# bga_test.net
KiCad netlist of a schematic drawn in EAGLE
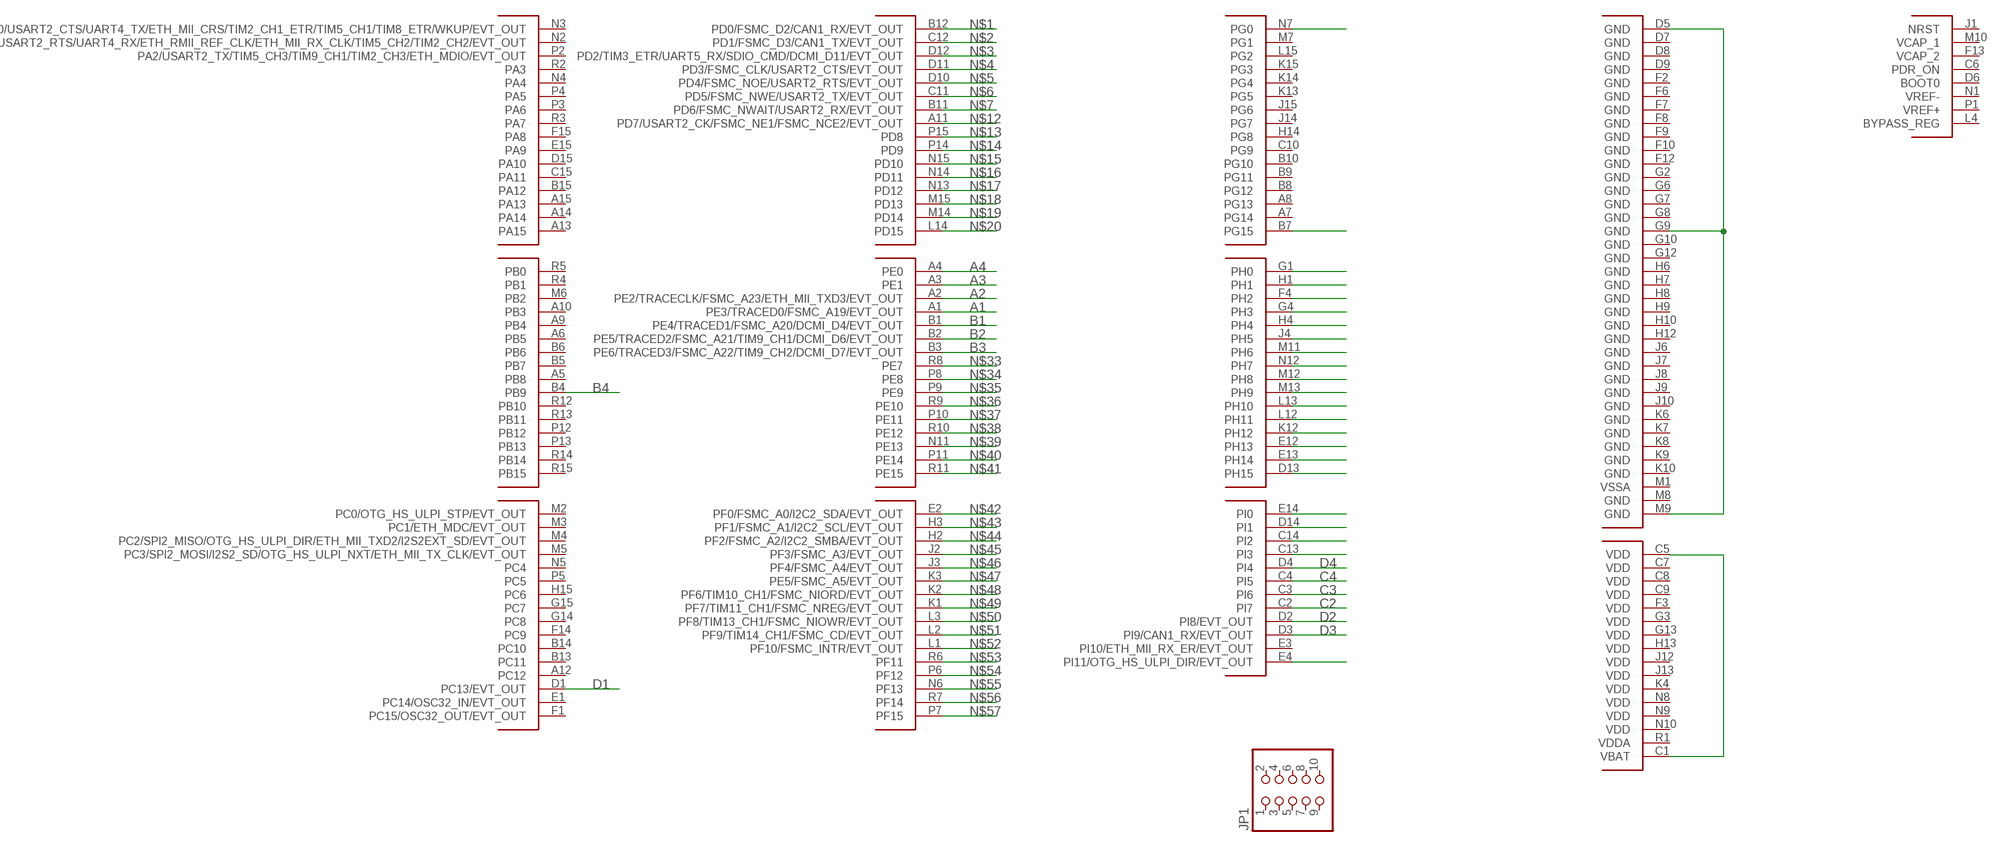
[diagram p0: schematic, sheet 1]
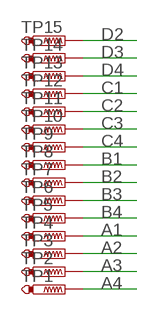
[diagram p1: schematic, sheet 2]

(export (version "E")
  (design (tool "Eeschema 10.0.6"))
  (components
    (comp (ref "TP1")
      (value "PTR1TP06R")
      (footprint "eagle-import:TP06R")
      (libsource (lib "eagle-import") (part "PTR1TP06R"))
    )
    (comp (ref "TP2")
      (value "PTR1TP06R")
      (footprint "eagle-import:TP06R")
      (libsource (lib "eagle-import") (part "PTR1TP06R"))
    )
    (comp (ref "TP3")
      (value "PTR1TP06R")
      (footprint "eagle-import:TP06R")
      (libsource (lib "eagle-import") (part "PTR1TP06R"))
    )
    (comp (ref "TP4")
      (value "PTR1TP06R")
      (footprint "eagle-import:TP06R")
      (libsource (lib "eagle-import") (part "PTR1TP06R"))
    )
    (comp (ref "TP5")
      (value "PTR1TP06R")
      (footprint "eagle-import:TP06R")
      (libsource (lib "eagle-import") (part "PTR1TP06R"))
    )
    (comp (ref "TP6")
      (value "PTR1TP06R")
      (footprint "eagle-import:TP06R")
      (libsource (lib "eagle-import") (part "PTR1TP06R"))
    )
    (comp (ref "TP7")
      (value "PTR1TP06R")
      (footprint "eagle-import:TP06R")
      (libsource (lib "eagle-import") (part "PTR1TP06R"))
    )
    (comp (ref "TP8")
      (value "PTR1TP06R")
      (footprint "eagle-import:TP06R")
      (libsource (lib "eagle-import") (part "PTR1TP06R"))
    )
    (comp (ref "TP9")
      (value "PTR1TP06R")
      (footprint "eagle-import:TP06R")
      (libsource (lib "eagle-import") (part "PTR1TP06R"))
    )
    (comp (ref "TP10")
      (value "PTR1TP06R")
      (footprint "eagle-import:TP06R")
      (libsource (lib "eagle-import") (part "PTR1TP06R"))
    )
    (comp (ref "TP11")
      (value "PTR1TP06R")
      (footprint "eagle-import:TP06R")
      (libsource (lib "eagle-import") (part "PTR1TP06R"))
    )
    (comp (ref "TP12")
      (value "PTR1TP06R")
      (footprint "eagle-import:TP06R")
      (libsource (lib "eagle-import") (part "PTR1TP06R"))
    )
    (comp (ref "TP13")
      (value "PTR1TP06R")
      (footprint "eagle-import:TP06R")
      (libsource (lib "eagle-import") (part "PTR1TP06R"))
    )
    (comp (ref "TP14")
      (value "PTR1TP06R")
      (footprint "eagle-import:TP06R")
      (libsource (lib "eagle-import") (part "PTR1TP06R"))
    )
    (comp (ref "TP15")
      (value "PTR1TP06R")
      (footprint "eagle-import:TP06R")
      (libsource (lib "eagle-import") (part "PTR1TP06R"))
    )
    (comp (ref "JP1")
      (value "PINHD-2X5")
      (footprint "eagle-import:2X05")
      (libsource (lib "eagle-import") (part "PINHD-2X5"))
    )
    (comp (ref "U$1")
      (value "STM32_32BIT_MCU_STM32F407IG")
      (footprint "eagle-import:STM32_32BIT_MCU_UFBGA176+25")
      (libsource (lib "eagle-import") (part "STM32_32BIT_MCU_STM32F407IG"))
    )
  )
  (nets
    (net (code "1") (name "A1") (class "Default")
      (node (ref "TP4") (pin "TP") (pinfunction "TP_TP") (pintype "input"))
      (node (ref "U$1") (pin "A1") (pinfunction "PE3/TRACED0/FSMC_A19/EVT_OUT_A1") (pintype "bidirectional"))
    )
    (net (code "2") (name "A2") (class "Default")
      (node (ref "TP3") (pin "TP") (pinfunction "TP_TP") (pintype "input"))
      (node (ref "U$1") (pin "A2") (pinfunction "PE2/TRACECLK/FSMC_A23/ETH_MII_TXD3/EVT_OUT_A2") (pintype "bidirectional"))
    )
    (net (code "3") (name "A3") (class "Default")
      (node (ref "TP2") (pin "TP") (pinfunction "TP_TP") (pintype "input"))
      (node (ref "U$1") (pin "A3") (pinfunction "PE1_A3") (pintype "bidirectional"))
    )
    (net (code "4") (name "A4") (class "Default")
      (node (ref "TP1") (pin "TP") (pinfunction "TP_TP") (pintype "input"))
      (node (ref "U$1") (pin "A4") (pinfunction "PE0_A4") (pintype "bidirectional"))
    )
    (net (code "5") (name "B1") (class "Default")
      (node (ref "TP8") (pin "TP") (pinfunction "TP_TP") (pintype "input"))
      (node (ref "U$1") (pin "B1") (pinfunction "PE4/TRACED1/FSMC_A20/DCMI_D4/EVT_OUT_B1") (pintype "bidirectional"))
    )
    (net (code "6") (name "B2") (class "Default")
      (node (ref "TP7") (pin "TP") (pinfunction "TP_TP") (pintype "input"))
      (node (ref "U$1") (pin "B2") (pinfunction "PE5/TRACED2/FSMC_A21/TIM9_CH1/DCMI_D6/EVT_OUT_B2") (pintype "bidirectional"))
    )
    (net (code "7") (name "B3") (class "Default")
      (node (ref "TP6") (pin "TP") (pinfunction "TP_TP") (pintype "input"))
      (node (ref "U$1") (pin "B3") (pinfunction "PE6/TRACED3/FSMC_A22/TIM9_CH2/DCMI_D7/EVT_OUT_B3") (pintype "bidirectional"))
    )
    (net (code "8") (name "B4") (class "Default")
      (node (ref "TP5") (pin "TP") (pinfunction "TP_TP") (pintype "input"))
      (node (ref "U$1") (pin "B4") (pinfunction "PB9_B4") (pintype "bidirectional"))
    )
    (net (code "9") (name "C1") (class "Default")
      (node (ref "TP12") (pin "TP") (pinfunction "TP_TP") (pintype "input"))
    )
    (net (code "10") (name "C2") (class "Default")
      (node (ref "TP11") (pin "TP") (pinfunction "TP_TP") (pintype "input"))
      (node (ref "U$1") (pin "C2") (pinfunction "PI7_C2") (pintype "bidirectional"))
    )
    (net (code "11") (name "C3") (class "Default")
      (node (ref "TP10") (pin "TP") (pinfunction "TP_TP") (pintype "input"))
      (node (ref "U$1") (pin "C3") (pinfunction "PI6_C3") (pintype "bidirectional"))
    )
    (net (code "12") (name "C4") (class "Default")
      (node (ref "TP9") (pin "TP") (pinfunction "TP_TP") (pintype "input"))
      (node (ref "U$1") (pin "C4") (pinfunction "PI5_C4") (pintype "bidirectional"))
    )
    (net (code "13") (name "D1") (class "Default")
      (node (ref "U$1") (pin "D1") (pinfunction "PC13/EVT_OUT_D1") (pintype "bidirectional"))
    )
    (net (code "14") (name "D2") (class "Default")
      (node (ref "TP15") (pin "TP") (pinfunction "TP_TP") (pintype "input"))
      (node (ref "U$1") (pin "D2") (pinfunction "PI8/EVT_OUT_D2") (pintype "bidirectional"))
    )
    (net (code "15") (name "D3") (class "Default")
      (node (ref "TP14") (pin "TP") (pinfunction "TP_TP") (pintype "input"))
      (node (ref "U$1") (pin "D3") (pinfunction "PI9/CAN1_RX/EVT_OUT_D3") (pintype "bidirectional"))
    )
    (net (code "16") (name "D4") (class "Default")
      (node (ref "TP13") (pin "TP") (pinfunction "TP_TP") (pintype "input"))
      (node (ref "U$1") (pin "D4") (pinfunction "PI4_D4") (pintype "bidirectional"))
    )
    (net (code "17") (name "N$1") (class "Default")
      (node (ref "U$1") (pin "B12") (pinfunction "PD0/FSMC_D2/CAN1_RX/EVT_OUT_B12") (pintype "bidirectional"))
    )
    (net (code "18") (name "N$2") (class "Default")
      (node (ref "U$1") (pin "C12") (pinfunction "PD1/FSMC_D3/CAN1_TX/EVT_OUT_C12") (pintype "bidirectional"))
    )
    (net (code "19") (name "N$3") (class "Default")
      (node (ref "U$1") (pin "D12") (pinfunction "PD2/TIM3_ETR/UART5_RX/SDIO_CMD/DCMI_D11/EVT_OUT_D12") (pintype "bidirectional"))
    )
    (net (code "20") (name "N$4") (class "Default")
      (node (ref "U$1") (pin "D11") (pinfunction "PD3/FSMC_CLK/USART2_CTS/EVT_OUT_D11") (pintype "bidirectional"))
    )
    (net (code "21") (name "N$5") (class "Default")
      (node (ref "U$1") (pin "D10") (pinfunction "PD4/FSMC_NOE/USART2_RTS/EVT_OUT_D10") (pintype "bidirectional"))
    )
    (net (code "22") (name "N$6") (class "Default")
      (node (ref "U$1") (pin "C11") (pinfunction "PD5/FSMC_NWE/USART2_TX/EVT_OUT_C11") (pintype "bidirectional"))
    )
    (net (code "23") (name "N$7") (class "Default")
      (node (ref "U$1") (pin "B11") (pinfunction "PD6/FSMC_NWAIT/USART2_RX/EVT_OUT_B11") (pintype "bidirectional"))
    )
    (net (code "24") (name "N$12") (class "Default")
      (node (ref "U$1") (pin "A11") (pinfunction "PD7/USART2_CK/FSMC_NE1/FSMC_NCE2/EVT_OUT_A11") (pintype "bidirectional"))
    )
    (net (code "25") (name "N$13") (class "Default")
      (node (ref "U$1") (pin "P15") (pinfunction "PD8_P15") (pintype "bidirectional"))
    )
    (net (code "26") (name "N$14") (class "Default")
      (node (ref "U$1") (pin "P14") (pinfunction "PD9_P14") (pintype "bidirectional"))
    )
    (net (code "27") (name "N$15") (class "Default")
      (node (ref "U$1") (pin "N15") (pinfunction "PD10_N15") (pintype "bidirectional"))
    )
    (net (code "28") (name "N$16") (class "Default")
      (node (ref "U$1") (pin "N14") (pinfunction "PD11_N14") (pintype "bidirectional"))
    )
    (net (code "29") (name "N$17") (class "Default")
      (node (ref "U$1") (pin "N13") (pinfunction "PD12_N13") (pintype "bidirectional"))
    )
    (net (code "30") (name "N$18") (class "Default")
      (node (ref "U$1") (pin "M15") (pinfunction "PD13_M15") (pintype "bidirectional"))
    )
    (net (code "31") (name "N$19") (class "Default")
      (node (ref "U$1") (pin "M14") (pinfunction "PD14_M14") (pintype "bidirectional"))
    )
    (net (code "32") (name "N$20") (class "Default")
      (node (ref "U$1") (pin "L14") (pinfunction "PD15_L14") (pintype "bidirectional"))
    )
    (net (code "33") (name "N$33") (class "Default")
      (node (ref "U$1") (pin "R8") (pinfunction "PE7_R8") (pintype "bidirectional"))
    )
    (net (code "34") (name "N$34") (class "Default")
      (node (ref "U$1") (pin "P8") (pinfunction "PE8_P8") (pintype "bidirectional"))
    )
    (net (code "35") (name "N$35") (class "Default")
      (node (ref "U$1") (pin "P9") (pinfunction "PE9_P9") (pintype "bidirectional"))
    )
    (net (code "36") (name "N$36") (class "Default")
      (node (ref "U$1") (pin "R9") (pinfunction "PE10_R9") (pintype "bidirectional"))
    )
    (net (code "37") (name "N$37") (class "Default")
      (node (ref "U$1") (pin "P10") (pinfunction "PE11_P10") (pintype "bidirectional"))
    )
    (net (code "38") (name "N$38") (class "Default")
      (node (ref "U$1") (pin "R10") (pinfunction "PE12_R10") (pintype "bidirectional"))
    )
    (net (code "39") (name "N$39") (class "Default")
      (node (ref "U$1") (pin "N11") (pinfunction "PE13_N11") (pintype "bidirectional"))
    )
    (net (code "40") (name "N$40") (class "Default")
      (node (ref "U$1") (pin "P11") (pinfunction "PE14_P11") (pintype "bidirectional"))
    )
    (net (code "41") (name "N$41") (class "Default")
      (node (ref "U$1") (pin "R11") (pinfunction "PE15_R11") (pintype "bidirectional"))
    )
    (net (code "42") (name "N$42") (class "Default")
      (node (ref "U$1") (pin "E2") (pinfunction "PF0/FSMC_A0/I2C2_SDA/EVT_OUT_E2") (pintype "bidirectional"))
    )
    (net (code "43") (name "N$43") (class "Default")
      (node (ref "U$1") (pin "H3") (pinfunction "PF1/FSMC_A1/I2C2_SCL/EVT_OUT_H3") (pintype "bidirectional"))
    )
    (net (code "44") (name "N$44") (class "Default")
      (node (ref "U$1") (pin "H2") (pinfunction "PF2/FSMC_A2/I2C2_SMBA/EVT_OUT_H2") (pintype "bidirectional"))
    )
    (net (code "45") (name "N$45") (class "Default")
      (node (ref "U$1") (pin "J2") (pinfunction "PF3/FSMC_A3/EVT_OUT_J2") (pintype "bidirectional"))
    )
    (net (code "46") (name "N$46") (class "Default")
      (node (ref "U$1") (pin "J3") (pinfunction "PF4/FSMC_A4/EVT_OUT_J3") (pintype "bidirectional"))
    )
    (net (code "47") (name "N$47") (class "Default")
      (node (ref "U$1") (pin "K3") (pinfunction "PE5/FSMC_A5/EVT_OUT_K3") (pintype "bidirectional"))
    )
    (net (code "48") (name "N$48") (class "Default")
      (node (ref "U$1") (pin "K2") (pinfunction "PF6/TIM10_CH1/FSMC_NIORD/EVT_OUT_K2") (pintype "bidirectional"))
    )
    (net (code "49") (name "N$49") (class "Default")
      (node (ref "U$1") (pin "K1") (pinfunction "PF7/TIM11_CH1/FSMC_NREG/EVT_OUT_K1") (pintype "bidirectional"))
    )
    (net (code "50") (name "N$50") (class "Default")
      (node (ref "U$1") (pin "L3") (pinfunction "PF8/TIM13_CH1/FSMC_NIOWR/EVT_OUT_L3") (pintype "bidirectional"))
    )
    (net (code "51") (name "N$51") (class "Default")
      (node (ref "U$1") (pin "L2") (pinfunction "PF9/TIM14_CH1/FSMC_CD/EVT_OUT_L2") (pintype "bidirectional"))
    )
    (net (code "52") (name "N$52") (class "Default")
      (node (ref "U$1") (pin "L1") (pinfunction "PF10/FSMC_INTR/EVT_OUT_L1") (pintype "bidirectional"))
    )
    (net (code "53") (name "N$53") (class "Default")
      (node (ref "U$1") (pin "R6") (pinfunction "PF11_R6") (pintype "bidirectional"))
    )
    (net (code "54") (name "N$54") (class "Default")
      (node (ref "U$1") (pin "P6") (pinfunction "PF12_P6") (pintype "bidirectional"))
    )
    (net (code "55") (name "N$55") (class "Default")
      (node (ref "U$1") (pin "N6") (pinfunction "PF13_N6") (pintype "bidirectional"))
    )
    (net (code "56") (name "N$56") (class "Default")
      (node (ref "U$1") (pin "R7") (pinfunction "PF14_R7") (pintype "bidirectional"))
    )
    (net (code "57") (name "N$57") (class "Default")
      (node (ref "U$1") (pin "P7") (pinfunction "PF15_P7") (pintype "bidirectional"))
    )
    (net (code "58") (name "Net-(U$1-GND-PadD5)") (class "Default")
      (node (ref "U$1") (pin "D5") (pinfunction "GND_D5") (pintype "bidirectional"))
      (node (ref "U$1") (pin "G9") (pinfunction "GND_G9") (pintype "bidirectional"))
      (node (ref "U$1") (pin "M9") (pinfunction "GND_M9") (pintype "bidirectional"))
    )
    (net (code "59") (name "Net-(U$1-VBAT)") (class "Default")
      (node (ref "U$1") (pin "C1") (pinfunction "VBAT_C1") (pintype "bidirectional"))
      (node (ref "U$1") (pin "C5") (pinfunction "VDD_C5") (pintype "bidirectional"))
    )
    (net (code "60") (name "unconnected-(JP1-Pad1)") (class "Default")
      (node (ref "JP1") (pin "1") (pinfunction "1_1") (pintype "passive"))
    )
    (net (code "61") (name "unconnected-(JP1-Pad2)") (class "Default")
      (node (ref "JP1") (pin "2") (pinfunction "2_2") (pintype "passive"))
    )
    (net (code "62") (name "unconnected-(JP1-Pad3)") (class "Default")
      (node (ref "JP1") (pin "3") (pinfunction "3_3") (pintype "passive"))
    )
    (net (code "63") (name "unconnected-(JP1-Pad4)") (class "Default")
      (node (ref "JP1") (pin "4") (pinfunction "4_4") (pintype "passive"))
    )
    (net (code "64") (name "unconnected-(JP1-Pad5)") (class "Default")
      (node (ref "JP1") (pin "5") (pinfunction "5_5") (pintype "passive"))
    )
    (net (code "65") (name "unconnected-(JP1-Pad6)") (class "Default")
      (node (ref "JP1") (pin "6") (pinfunction "6_6") (pintype "passive"))
    )
    (net (code "66") (name "unconnected-(JP1-Pad7)") (class "Default")
      (node (ref "JP1") (pin "7") (pinfunction "7_7") (pintype "passive"))
    )
    (net (code "67") (name "unconnected-(JP1-Pad8)") (class "Default")
      (node (ref "JP1") (pin "8") (pinfunction "8_8") (pintype "passive"))
    )
    (net (code "68") (name "unconnected-(JP1-Pad9)") (class "Default")
      (node (ref "JP1") (pin "9") (pinfunction "9_9") (pintype "passive"))
    )
    (net (code "69") (name "unconnected-(JP1-Pad10)") (class "Default")
      (node (ref "JP1") (pin "10") (pinfunction "10_10") (pintype "passive"))
    )
    (net (code "70") (name "unconnected-(U$1-BOOT0-PadD6)") (class "Default")
      (node (ref "U$1") (pin "D6") (pinfunction "BOOT0_D6") (pintype "bidirectional"))
    )
    (net (code "71") (name "unconnected-(U$1-BYPASS_REG-PadL4)") (class "Default")
      (node (ref "U$1") (pin "L4") (pinfunction "BYPASS_REG_L4") (pintype "bidirectional"))
    )
    (net (code "72") (name "unconnected-(U$1-GND-PadD7)") (class "Default")
      (node (ref "U$1") (pin "D7") (pinfunction "GND_D7") (pintype "bidirectional"))
    )
    (net (code "73") (name "unconnected-(U$1-GND-PadD8)") (class "Default")
      (node (ref "U$1") (pin "D8") (pinfunction "GND_D8") (pintype "bidirectional"))
    )
    (net (code "74") (name "unconnected-(U$1-GND-PadD9)") (class "Default")
      (node (ref "U$1") (pin "D9") (pinfunction "GND_D9") (pintype "bidirectional"))
    )
    (net (code "75") (name "unconnected-(U$1-GND-PadF2)") (class "Default")
      (node (ref "U$1") (pin "F2") (pinfunction "GND_F2") (pintype "bidirectional"))
    )
    (net (code "76") (name "unconnected-(U$1-GND-PadF6)") (class "Default")
      (node (ref "U$1") (pin "F6") (pinfunction "GND_F6") (pintype "bidirectional"))
    )
    (net (code "77") (name "unconnected-(U$1-GND-PadF7)") (class "Default")
      (node (ref "U$1") (pin "F7") (pinfunction "GND_F7") (pintype "bidirectional"))
    )
    (net (code "78") (name "unconnected-(U$1-GND-PadF8)") (class "Default")
      (node (ref "U$1") (pin "F8") (pinfunction "GND_F8") (pintype "bidirectional"))
    )
    (net (code "79") (name "unconnected-(U$1-GND-PadF9)") (class "Default")
      (node (ref "U$1") (pin "F9") (pinfunction "GND_F9") (pintype "bidirectional"))
    )
    (net (code "80") (name "unconnected-(U$1-GND-PadF10)") (class "Default")
      (node (ref "U$1") (pin "F10") (pinfunction "GND_F10") (pintype "bidirectional"))
    )
    (net (code "81") (name "unconnected-(U$1-GND-PadF12)") (class "Default")
      (node (ref "U$1") (pin "F12") (pinfunction "GND_F12") (pintype "bidirectional"))
    )
    (net (code "82") (name "unconnected-(U$1-GND-PadG2)") (class "Default")
      (node (ref "U$1") (pin "G2") (pinfunction "GND_G2") (pintype "bidirectional"))
    )
    (net (code "83") (name "unconnected-(U$1-GND-PadG6)") (class "Default")
      (node (ref "U$1") (pin "G6") (pinfunction "GND_G6") (pintype "bidirectional"))
    )
    (net (code "84") (name "unconnected-(U$1-GND-PadG7)") (class "Default")
      (node (ref "U$1") (pin "G7") (pinfunction "GND_G7") (pintype "bidirectional"))
    )
    (net (code "85") (name "unconnected-(U$1-GND-PadG8)") (class "Default")
      (node (ref "U$1") (pin "G8") (pinfunction "GND_G8") (pintype "bidirectional"))
    )
    (net (code "86") (name "unconnected-(U$1-GND-PadG10)") (class "Default")
      (node (ref "U$1") (pin "G10") (pinfunction "GND_G10") (pintype "bidirectional"))
    )
    (net (code "87") (name "unconnected-(U$1-GND-PadG12)") (class "Default")
      (node (ref "U$1") (pin "G12") (pinfunction "GND_G12") (pintype "bidirectional"))
    )
    (net (code "88") (name "unconnected-(U$1-GND-PadH6)") (class "Default")
      (node (ref "U$1") (pin "H6") (pinfunction "GND_H6") (pintype "bidirectional"))
    )
    (net (code "89") (name "unconnected-(U$1-GND-PadH7)") (class "Default")
      (node (ref "U$1") (pin "H7") (pinfunction "GND_H7") (pintype "bidirectional"))
    )
    (net (code "90") (name "unconnected-(U$1-GND-PadH8)") (class "Default")
      (node (ref "U$1") (pin "H8") (pinfunction "GND_H8") (pintype "bidirectional"))
    )
    (net (code "91") (name "unconnected-(U$1-GND-PadH9)") (class "Default")
      (node (ref "U$1") (pin "H9") (pinfunction "GND_H9") (pintype "bidirectional"))
    )
    (net (code "92") (name "unconnected-(U$1-GND-PadH10)") (class "Default")
      (node (ref "U$1") (pin "H10") (pinfunction "GND_H10") (pintype "bidirectional"))
    )
    (net (code "93") (name "unconnected-(U$1-GND-PadH12)") (class "Default")
      (node (ref "U$1") (pin "H12") (pinfunction "GND_H12") (pintype "bidirectional"))
    )
    (net (code "94") (name "unconnected-(U$1-GND-PadJ6)") (class "Default")
      (node (ref "U$1") (pin "J6") (pinfunction "GND_J6") (pintype "bidirectional"))
    )
    (net (code "95") (name "unconnected-(U$1-GND-PadJ7)") (class "Default")
      (node (ref "U$1") (pin "J7") (pinfunction "GND_J7") (pintype "bidirectional"))
    )
    (net (code "96") (name "unconnected-(U$1-GND-PadJ8)") (class "Default")
      (node (ref "U$1") (pin "J8") (pinfunction "GND_J8") (pintype "bidirectional"))
    )
    (net (code "97") (name "unconnected-(U$1-GND-PadJ9)") (class "Default")
      (node (ref "U$1") (pin "J9") (pinfunction "GND_J9") (pintype "bidirectional"))
    )
    (net (code "98") (name "unconnected-(U$1-GND-PadJ10)") (class "Default")
      (node (ref "U$1") (pin "J10") (pinfunction "GND_J10") (pintype "bidirectional"))
    )
    (net (code "99") (name "unconnected-(U$1-GND-PadK6)") (class "Default")
      (node (ref "U$1") (pin "K6") (pinfunction "GND_K6") (pintype "bidirectional"))
    )
    (net (code "100") (name "unconnected-(U$1-GND-PadK7)") (class "Default")
      (node (ref "U$1") (pin "K7") (pinfunction "GND_K7") (pintype "bidirectional"))
    )
    (net (code "101") (name "unconnected-(U$1-GND-PadK8)") (class "Default")
      (node (ref "U$1") (pin "K8") (pinfunction "GND_K8") (pintype "bidirectional"))
    )
    (net (code "102") (name "unconnected-(U$1-GND-PadK9)") (class "Default")
      (node (ref "U$1") (pin "K9") (pinfunction "GND_K9") (pintype "bidirectional"))
    )
    (net (code "103") (name "unconnected-(U$1-GND-PadK10)") (class "Default")
      (node (ref "U$1") (pin "K10") (pinfunction "GND_K10") (pintype "bidirectional"))
    )
    (net (code "104") (name "unconnected-(U$1-GND-PadM8)") (class "Default")
      (node (ref "U$1") (pin "M8") (pinfunction "GND_M8") (pintype "bidirectional"))
    )
    (net (code "105") (name "unconnected-(U$1-NRST-PadJ1)") (class "Default")
      (node (ref "U$1") (pin "J1") (pinfunction "NRST_J1") (pintype "bidirectional"))
    )
    (net (code "106") (name "unconnected-(U$1-PA0{slash}USART2_CTS{slash}UART4_TX{slash}ETH_MII_CRS{slash}TIM2_CH1_ETR{slash}TIM5_CH1{slash}TIM8_ETR{slash}WKUP{slash}EVT_OUT-PadN3)") (class "Default")
      (node (ref "U$1") (pin "N3") (pinfunction "PA0/USART2_CTS/UART4_TX/ETH_MII_CRS/TIM2_CH1_ETR/TIM5_CH1/TIM8_ETR/WKUP/EVT_OUT_N3") (pintype "bidirectional"))
    )
    (net (code "107") (name "unconnected-(U$1-PA1{slash}USART2_RTS{slash}UART4_RX{slash}ETH_RMII_REF_CLK{slash}ETH_MII_RX_CLK{slash}TIM5_CH2{slash}TIM2_CH2{slash}EVT_OUT-PadN2)") (class "Default")
      (node (ref "U$1") (pin "N2") (pinfunction "PA1/USART2_RTS/UART4_RX/ETH_RMII_REF_CLK/ETH_MII_RX_CLK/TIM5_CH2/TIM2_CH2/EVT_OUT_N2") (pintype "bidirectional"))
    )
    (net (code "108") (name "unconnected-(U$1-PA2{slash}USART2_TX{slash}TIM5_CH3{slash}TIM9_CH1{slash}TIM2_CH3{slash}ETH_MDIO{slash}EVT_OUT-PadP2)") (class "Default")
      (node (ref "U$1") (pin "P2") (pinfunction "PA2/USART2_TX/TIM5_CH3/TIM9_CH1/TIM2_CH3/ETH_MDIO/EVT_OUT_P2") (pintype "bidirectional"))
    )
    (net (code "109") (name "unconnected-(U$1-PA3-PadR2)") (class "Default")
      (node (ref "U$1") (pin "R2") (pinfunction "PA3_R2") (pintype "bidirectional"))
    )
    (net (code "110") (name "unconnected-(U$1-PA4-PadN4)") (class "Default")
      (node (ref "U$1") (pin "N4") (pinfunction "PA4_N4") (pintype "bidirectional"))
    )
    (net (code "111") (name "unconnected-(U$1-PA5-PadP4)") (class "Default")
      (node (ref "U$1") (pin "P4") (pinfunction "PA5_P4") (pintype "bidirectional"))
    )
    (net (code "112") (name "unconnected-(U$1-PA6-PadP3)") (class "Default")
      (node (ref "U$1") (pin "P3") (pinfunction "PA6_P3") (pintype "bidirectional"))
    )
    (net (code "113") (name "unconnected-(U$1-PA7-PadR3)") (class "Default")
      (node (ref "U$1") (pin "R3") (pinfunction "PA7_R3") (pintype "bidirectional"))
    )
    (net (code "114") (name "unconnected-(U$1-PA8-PadF15)") (class "Default")
      (node (ref "U$1") (pin "F15") (pinfunction "PA8_F15") (pintype "bidirectional"))
    )
    (net (code "115") (name "unconnected-(U$1-PA9-PadE15)") (class "Default")
      (node (ref "U$1") (pin "E15") (pinfunction "PA9_E15") (pintype "bidirectional"))
    )
    (net (code "116") (name "unconnected-(U$1-PA10-PadD15)") (class "Default")
      (node (ref "U$1") (pin "D15") (pinfunction "PA10_D15") (pintype "bidirectional"))
    )
    (net (code "117") (name "unconnected-(U$1-PA11-PadC15)") (class "Default")
      (node (ref "U$1") (pin "C15") (pinfunction "PA11_C15") (pintype "bidirectional"))
    )
    (net (code "118") (name "unconnected-(U$1-PA12-PadB15)") (class "Default")
      (node (ref "U$1") (pin "B15") (pinfunction "PA12_B15") (pintype "bidirectional"))
    )
    (net (code "119") (name "unconnected-(U$1-PA13-PadA15)") (class "Default")
      (node (ref "U$1") (pin "A15") (pinfunction "PA13_A15") (pintype "bidirectional"))
    )
    (net (code "120") (name "unconnected-(U$1-PA14-PadA14)") (class "Default")
      (node (ref "U$1") (pin "A14") (pinfunction "PA14_A14") (pintype "bidirectional"))
    )
    (net (code "121") (name "unconnected-(U$1-PA15-PadA13)") (class "Default")
      (node (ref "U$1") (pin "A13") (pinfunction "PA15_A13") (pintype "bidirectional"))
    )
    (net (code "122") (name "unconnected-(U$1-PB0-PadR5)") (class "Default")
      (node (ref "U$1") (pin "R5") (pinfunction "PB0_R5") (pintype "bidirectional"))
    )
    (net (code "123") (name "unconnected-(U$1-PB1-PadR4)") (class "Default")
      (node (ref "U$1") (pin "R4") (pinfunction "PB1_R4") (pintype "bidirectional"))
    )
    (net (code "124") (name "unconnected-(U$1-PB2-PadM6)") (class "Default")
      (node (ref "U$1") (pin "M6") (pinfunction "PB2_M6") (pintype "bidirectional"))
    )
    (net (code "125") (name "unconnected-(U$1-PB3-PadA10)") (class "Default")
      (node (ref "U$1") (pin "A10") (pinfunction "PB3_A10") (pintype "bidirectional"))
    )
    (net (code "126") (name "unconnected-(U$1-PB4-PadA9)") (class "Default")
      (node (ref "U$1") (pin "A9") (pinfunction "PB4_A9") (pintype "bidirectional"))
    )
    (net (code "127") (name "unconnected-(U$1-PB5-PadA6)") (class "Default")
      (node (ref "U$1") (pin "A6") (pinfunction "PB5_A6") (pintype "bidirectional"))
    )
    (net (code "128") (name "unconnected-(U$1-PB6-PadB6)") (class "Default")
      (node (ref "U$1") (pin "B6") (pinfunction "PB6_B6") (pintype "bidirectional"))
    )
    (net (code "129") (name "unconnected-(U$1-PB7-PadB5)") (class "Default")
      (node (ref "U$1") (pin "B5") (pinfunction "PB7_B5") (pintype "bidirectional"))
    )
    (net (code "130") (name "unconnected-(U$1-PB8-PadA5)") (class "Default")
      (node (ref "U$1") (pin "A5") (pinfunction "PB8_A5") (pintype "bidirectional"))
    )
    (net (code "131") (name "unconnected-(U$1-PB10-PadR12)") (class "Default")
      (node (ref "U$1") (pin "R12") (pinfunction "PB10_R12") (pintype "bidirectional"))
    )
    (net (code "132") (name "unconnected-(U$1-PB11-PadR13)") (class "Default")
      (node (ref "U$1") (pin "R13") (pinfunction "PB11_R13") (pintype "bidirectional"))
    )
    (net (code "133") (name "unconnected-(U$1-PB12-PadP12)") (class "Default")
      (node (ref "U$1") (pin "P12") (pinfunction "PB12_P12") (pintype "bidirectional"))
    )
    (net (code "134") (name "unconnected-(U$1-PB13-PadP13)") (class "Default")
      (node (ref "U$1") (pin "P13") (pinfunction "PB13_P13") (pintype "bidirectional"))
    )
    (net (code "135") (name "unconnected-(U$1-PB14-PadR14)") (class "Default")
      (node (ref "U$1") (pin "R14") (pinfunction "PB14_R14") (pintype "bidirectional"))
    )
    (net (code "136") (name "unconnected-(U$1-PB15-PadR15)") (class "Default")
      (node (ref "U$1") (pin "R15") (pinfunction "PB15_R15") (pintype "bidirectional"))
    )
    (net (code "137") (name "unconnected-(U$1-PC0{slash}OTG_HS_ULPI_STP{slash}EVT_OUT-PadM2)") (class "Default")
      (node (ref "U$1") (pin "M2") (pinfunction "PC0/OTG_HS_ULPI_STP/EVT_OUT_M2") (pintype "bidirectional"))
    )
    (net (code "138") (name "unconnected-(U$1-PC1{slash}ETH_MDC{slash}EVT_OUT-PadM3)") (class "Default")
      (node (ref "U$1") (pin "M3") (pinfunction "PC1/ETH_MDC/EVT_OUT_M3") (pintype "bidirectional"))
    )
    (net (code "139") (name "unconnected-(U$1-PC2{slash}SPI2_MISO{slash}OTG_HS_ULPI_DIR{slash}ETH_MII_TXD2{slash}I2S2EXT_SD{slash}EVT_OUT-PadM4)") (class "Default")
      (node (ref "U$1") (pin "M4") (pinfunction "PC2/SPI2_MISO/OTG_HS_ULPI_DIR/ETH_MII_TXD2/I2S2EXT_SD/EVT_OUT_M4") (pintype "bidirectional"))
    )
    (net (code "140") (name "unconnected-(U$1-PC3{slash}SPI2_MOSI{slash}I2S2_SD{slash}OTG_HS_ULPI_NXT{slash}ETH_MII_TX_CLK{slash}EVT_OUT-PadM5)") (class "Default")
      (node (ref "U$1") (pin "M5") (pinfunction "PC3/SPI2_MOSI/I2S2_SD/OTG_HS_ULPI_NXT/ETH_MII_TX_CLK/EVT_OUT_M5") (pintype "bidirectional"))
    )
    (net (code "141") (name "unconnected-(U$1-PC4-PadN5)") (class "Default")
      (node (ref "U$1") (pin "N5") (pinfunction "PC4_N5") (pintype "bidirectional"))
    )
    (net (code "142") (name "unconnected-(U$1-PC5-PadP5)") (class "Default")
      (node (ref "U$1") (pin "P5") (pinfunction "PC5_P5") (pintype "bidirectional"))
    )
    (net (code "143") (name "unconnected-(U$1-PC6-PadH15)") (class "Default")
      (node (ref "U$1") (pin "H15") (pinfunction "PC6_H15") (pintype "bidirectional"))
    )
    (net (code "144") (name "unconnected-(U$1-PC7-PadG15)") (class "Default")
      (node (ref "U$1") (pin "G15") (pinfunction "PC7_G15") (pintype "bidirectional"))
    )
    (net (code "145") (name "unconnected-(U$1-PC8-PadG14)") (class "Default")
      (node (ref "U$1") (pin "G14") (pinfunction "PC8_G14") (pintype "bidirectional"))
    )
    (net (code "146") (name "unconnected-(U$1-PC9-PadF14)") (class "Default")
      (node (ref "U$1") (pin "F14") (pinfunction "PC9_F14") (pintype "bidirectional"))
    )
    (net (code "147") (name "unconnected-(U$1-PC10-PadB14)") (class "Default")
      (node (ref "U$1") (pin "B14") (pinfunction "PC10_B14") (pintype "bidirectional"))
    )
    (net (code "148") (name "unconnected-(U$1-PC11-PadB13)") (class "Default")
      (node (ref "U$1") (pin "B13") (pinfunction "PC11_B13") (pintype "bidirectional"))
    )
    (net (code "149") (name "unconnected-(U$1-PC12-PadA12)") (class "Default")
      (node (ref "U$1") (pin "A12") (pinfunction "PC12_A12") (pintype "bidirectional"))
    )
    (net (code "150") (name "unconnected-(U$1-PC14{slash}OSC32_IN{slash}EVT_OUT-PadE1)") (class "Default")
      (node (ref "U$1") (pin "E1") (pinfunction "PC14/OSC32_IN/EVT_OUT_E1") (pintype "bidirectional"))
    )
    (net (code "151") (name "unconnected-(U$1-PC15{slash}OSC32_OUT{slash}EVT_OUT-PadF1)") (class "Default")
      (node (ref "U$1") (pin "F1") (pinfunction "PC15/OSC32_OUT/EVT_OUT_F1") (pintype "bidirectional"))
    )
    (net (code "152") (name "unconnected-(U$1-PDR_ON-PadC6)") (class "Default")
      (node (ref "U$1") (pin "C6") (pinfunction "PDR_ON_C6") (pintype "bidirectional"))
    )
    (net (code "153") (name "unconnected-(U$1-PG0-PadN7)") (class "Default")
      (node (ref "U$1") (pin "N7") (pinfunction "PG0_N7") (pintype "bidirectional"))
    )
    (net (code "154") (name "unconnected-(U$1-PG1-PadM7)") (class "Default")
      (node (ref "U$1") (pin "M7") (pinfunction "PG1_M7") (pintype "bidirectional"))
    )
    (net (code "155") (name "unconnected-(U$1-PG2-PadL15)") (class "Default")
      (node (ref "U$1") (pin "L15") (pinfunction "PG2_L15") (pintype "bidirectional"))
    )
    (net (code "156") (name "unconnected-(U$1-PG3-PadK15)") (class "Default")
      (node (ref "U$1") (pin "K15") (pinfunction "PG3_K15") (pintype "bidirectional"))
    )
    (net (code "157") (name "unconnected-(U$1-PG4-PadK14)") (class "Default")
      (node (ref "U$1") (pin "K14") (pinfunction "PG4_K14") (pintype "bidirectional"))
    )
    (net (code "158") (name "unconnected-(U$1-PG5-PadK13)") (class "Default")
      (node (ref "U$1") (pin "K13") (pinfunction "PG5_K13") (pintype "bidirectional"))
    )
    (net (code "159") (name "unconnected-(U$1-PG6-PadJ15)") (class "Default")
      (node (ref "U$1") (pin "J15") (pinfunction "PG6_J15") (pintype "bidirectional"))
    )
    (net (code "160") (name "unconnected-(U$1-PG7-PadJ14)") (class "Default")
      (node (ref "U$1") (pin "J14") (pinfunction "PG7_J14") (pintype "bidirectional"))
    )
    (net (code "161") (name "unconnected-(U$1-PG8-PadH14)") (class "Default")
      (node (ref "U$1") (pin "H14") (pinfunction "PG8_H14") (pintype "bidirectional"))
    )
    (net (code "162") (name "unconnected-(U$1-PG9-PadC10)") (class "Default")
      (node (ref "U$1") (pin "C10") (pinfunction "PG9_C10") (pintype "bidirectional"))
    )
    (net (code "163") (name "unconnected-(U$1-PG10-PadB10)") (class "Default")
      (node (ref "U$1") (pin "B10") (pinfunction "PG10_B10") (pintype "bidirectional"))
    )
    (net (code "164") (name "unconnected-(U$1-PG11-PadB9)") (class "Default")
      (node (ref "U$1") (pin "B9") (pinfunction "PG11_B9") (pintype "bidirectional"))
    )
    (net (code "165") (name "unconnected-(U$1-PG12-PadB8)") (class "Default")
      (node (ref "U$1") (pin "B8") (pinfunction "PG12_B8") (pintype "bidirectional"))
    )
    (net (code "166") (name "unconnected-(U$1-PG13-PadA8)") (class "Default")
      (node (ref "U$1") (pin "A8") (pinfunction "PG13_A8") (pintype "bidirectional"))
    )
    (net (code "167") (name "unconnected-(U$1-PG14-PadA7)") (class "Default")
      (node (ref "U$1") (pin "A7") (pinfunction "PG14_A7") (pintype "bidirectional"))
    )
    (net (code "168") (name "unconnected-(U$1-PG15-PadB7)") (class "Default")
      (node (ref "U$1") (pin "B7") (pinfunction "PG15_B7") (pintype "bidirectional"))
    )
    (net (code "169") (name "unconnected-(U$1-PH0-PadG1)") (class "Default")
      (node (ref "U$1") (pin "G1") (pinfunction "PH0_G1") (pintype "bidirectional"))
    )
    (net (code "170") (name "unconnected-(U$1-PH1-PadH1)") (class "Default")
      (node (ref "U$1") (pin "H1") (pinfunction "PH1_H1") (pintype "bidirectional"))
    )
    (net (code "171") (name "unconnected-(U$1-PH2-PadF4)") (class "Default")
      (node (ref "U$1") (pin "F4") (pinfunction "PH2_F4") (pintype "bidirectional"))
    )
    (net (code "172") (name "unconnected-(U$1-PH3-PadG4)") (class "Default")
      (node (ref "U$1") (pin "G4") (pinfunction "PH3_G4") (pintype "bidirectional"))
    )
    (net (code "173") (name "unconnected-(U$1-PH4-PadH4)") (class "Default")
      (node (ref "U$1") (pin "H4") (pinfunction "PH4_H4") (pintype "bidirectional"))
    )
    (net (code "174") (name "unconnected-(U$1-PH5-PadJ4)") (class "Default")
      (node (ref "U$1") (pin "J4") (pinfunction "PH5_J4") (pintype "bidirectional"))
    )
    (net (code "175") (name "unconnected-(U$1-PH6-PadM11)") (class "Default")
      (node (ref "U$1") (pin "M11") (pinfunction "PH6_M11") (pintype "bidirectional"))
    )
    (net (code "176") (name "unconnected-(U$1-PH7-PadN12)") (class "Default")
      (node (ref "U$1") (pin "N12") (pinfunction "PH7_N12") (pintype "bidirectional"))
    )
    (net (code "177") (name "unconnected-(U$1-PH8-PadM12)") (class "Default")
      (node (ref "U$1") (pin "M12") (pinfunction "PH8_M12") (pintype "bidirectional"))
    )
    (net (code "178") (name "unconnected-(U$1-PH9-PadM13)") (class "Default")
      (node (ref "U$1") (pin "M13") (pinfunction "PH9_M13") (pintype "bidirectional"))
    )
    (net (code "179") (name "unconnected-(U$1-PH10-PadL13)") (class "Default")
      (node (ref "U$1") (pin "L13") (pinfunction "PH10_L13") (pintype "bidirectional"))
    )
    (net (code "180") (name "unconnected-(U$1-PH11-PadL12)") (class "Default")
      (node (ref "U$1") (pin "L12") (pinfunction "PH11_L12") (pintype "bidirectional"))
    )
    (net (code "181") (name "unconnected-(U$1-PH12-PadK12)") (class "Default")
      (node (ref "U$1") (pin "K12") (pinfunction "PH12_K12") (pintype "bidirectional"))
    )
    (net (code "182") (name "unconnected-(U$1-PH13-PadE12)") (class "Default")
      (node (ref "U$1") (pin "E12") (pinfunction "PH13_E12") (pintype "bidirectional"))
    )
    (net (code "183") (name "unconnected-(U$1-PH14-PadE13)") (class "Default")
      (node (ref "U$1") (pin "E13") (pinfunction "PH14_E13") (pintype "bidirectional"))
    )
    (net (code "184") (name "unconnected-(U$1-PH15-PadD13)") (class "Default")
      (node (ref "U$1") (pin "D13") (pinfunction "PH15_D13") (pintype "bidirectional"))
    )
    (net (code "185") (name "unconnected-(U$1-PI0-PadE14)") (class "Default")
      (node (ref "U$1") (pin "E14") (pinfunction "PI0_E14") (pintype "bidirectional"))
    )
    (net (code "186") (name "unconnected-(U$1-PI1-PadD14)") (class "Default")
      (node (ref "U$1") (pin "D14") (pinfunction "PI1_D14") (pintype "bidirectional"))
    )
    (net (code "187") (name "unconnected-(U$1-PI2-PadC14)") (class "Default")
      (node (ref "U$1") (pin "C14") (pinfunction "PI2_C14") (pintype "bidirectional"))
    )
    (net (code "188") (name "unconnected-(U$1-PI3-PadC13)") (class "Default")
      (node (ref "U$1") (pin "C13") (pinfunction "PI3_C13") (pintype "bidirectional"))
    )
    (net (code "189") (name "unconnected-(U$1-PI10{slash}ETH_MII_RX_ER{slash}EVT_OUT-PadE3)") (class "Default")
      (node (ref "U$1") (pin "E3") (pinfunction "PI10/ETH_MII_RX_ER/EVT_OUT_E3") (pintype "bidirectional"))
    )
    (net (code "190") (name "unconnected-(U$1-PI11{slash}OTG_HS_ULPI_DIR{slash}EVT_OUT-PadE4)") (class "Default")
      (node (ref "U$1") (pin "E4") (pinfunction "PI11/OTG_HS_ULPI_DIR/EVT_OUT_E4") (pintype "bidirectional"))
    )
    (net (code "191") (name "unconnected-(U$1-VCAP_1-PadM10)") (class "Default")
      (node (ref "U$1") (pin "M10") (pinfunction "VCAP_1_M10") (pintype "bidirectional"))
    )
    (net (code "192") (name "unconnected-(U$1-VCAP_2-PadF13)") (class "Default")
      (node (ref "U$1") (pin "F13") (pinfunction "VCAP_2_F13") (pintype "bidirectional"))
    )
    (net (code "193") (name "unconnected-(U$1-VDD-PadC7)") (class "Default")
      (node (ref "U$1") (pin "C7") (pinfunction "VDD_C7") (pintype "bidirectional"))
    )
    (net (code "194") (name "unconnected-(U$1-VDD-PadC8)") (class "Default")
      (node (ref "U$1") (pin "C8") (pinfunction "VDD_C8") (pintype "bidirectional"))
    )
    (net (code "195") (name "unconnected-(U$1-VDD-PadC9)") (class "Default")
      (node (ref "U$1") (pin "C9") (pinfunction "VDD_C9") (pintype "bidirectional"))
    )
    (net (code "196") (name "unconnected-(U$1-VDD-PadF3)") (class "Default")
      (node (ref "U$1") (pin "F3") (pinfunction "VDD_F3") (pintype "bidirectional"))
    )
    (net (code "197") (name "unconnected-(U$1-VDD-PadG3)") (class "Default")
      (node (ref "U$1") (pin "G3") (pinfunction "VDD_G3") (pintype "bidirectional"))
    )
    (net (code "198") (name "unconnected-(U$1-VDD-PadG13)") (class "Default")
      (node (ref "U$1") (pin "G13") (pinfunction "VDD_G13") (pintype "bidirectional"))
    )
    (net (code "199") (name "unconnected-(U$1-VDD-PadH13)") (class "Default")
      (node (ref "U$1") (pin "H13") (pinfunction "VDD_H13") (pintype "bidirectional"))
    )
    (net (code "200") (name "unconnected-(U$1-VDD-PadJ12)") (class "Default")
      (node (ref "U$1") (pin "J12") (pinfunction "VDD_J12") (pintype "bidirectional"))
    )
    (net (code "201") (name "unconnected-(U$1-VDD-PadJ13)") (class "Default")
      (node (ref "U$1") (pin "J13") (pinfunction "VDD_J13") (pintype "bidirectional"))
    )
    (net (code "202") (name "unconnected-(U$1-VDD-PadK4)") (class "Default")
      (node (ref "U$1") (pin "K4") (pinfunction "VDD_K4") (pintype "bidirectional"))
    )
    (net (code "203") (name "unconnected-(U$1-VDD-PadN8)") (class "Default")
      (node (ref "U$1") (pin "N8") (pinfunction "VDD_N8") (pintype "bidirectional"))
    )
    (net (code "204") (name "unconnected-(U$1-VDD-PadN9)") (class "Default")
      (node (ref "U$1") (pin "N9") (pinfunction "VDD_N9") (pintype "bidirectional"))
    )
    (net (code "205") (name "unconnected-(U$1-VDD-PadN10)") (class "Default")
      (node (ref "U$1") (pin "N10") (pinfunction "VDD_N10") (pintype "bidirectional"))
    )
    (net (code "206") (name "unconnected-(U$1-VDDA-PadR1)") (class "Default")
      (node (ref "U$1") (pin "R1") (pinfunction "VDDA_R1") (pintype "bidirectional"))
    )
    (net (code "207") (name "unconnected-(U$1-VREF+-PadP1)") (class "Default")
      (node (ref "U$1") (pin "P1") (pinfunction "VREF+_P1") (pintype "bidirectional"))
    )
    (net (code "208") (name "unconnected-(U$1-VREF--PadN1)") (class "Default")
      (node (ref "U$1") (pin "N1") (pinfunction "VREF-_N1") (pintype "bidirectional"))
    )
    (net (code "209") (name "unconnected-(U$1-VSSA-PadM1)") (class "Default")
      (node (ref "U$1") (pin "M1") (pinfunction "VSSA_M1") (pintype "bidirectional"))
    )
  )
)
